# ArduinoUNO-VN_v1_1.net
KiCad netlist of a schematic drawn in Altium Designer
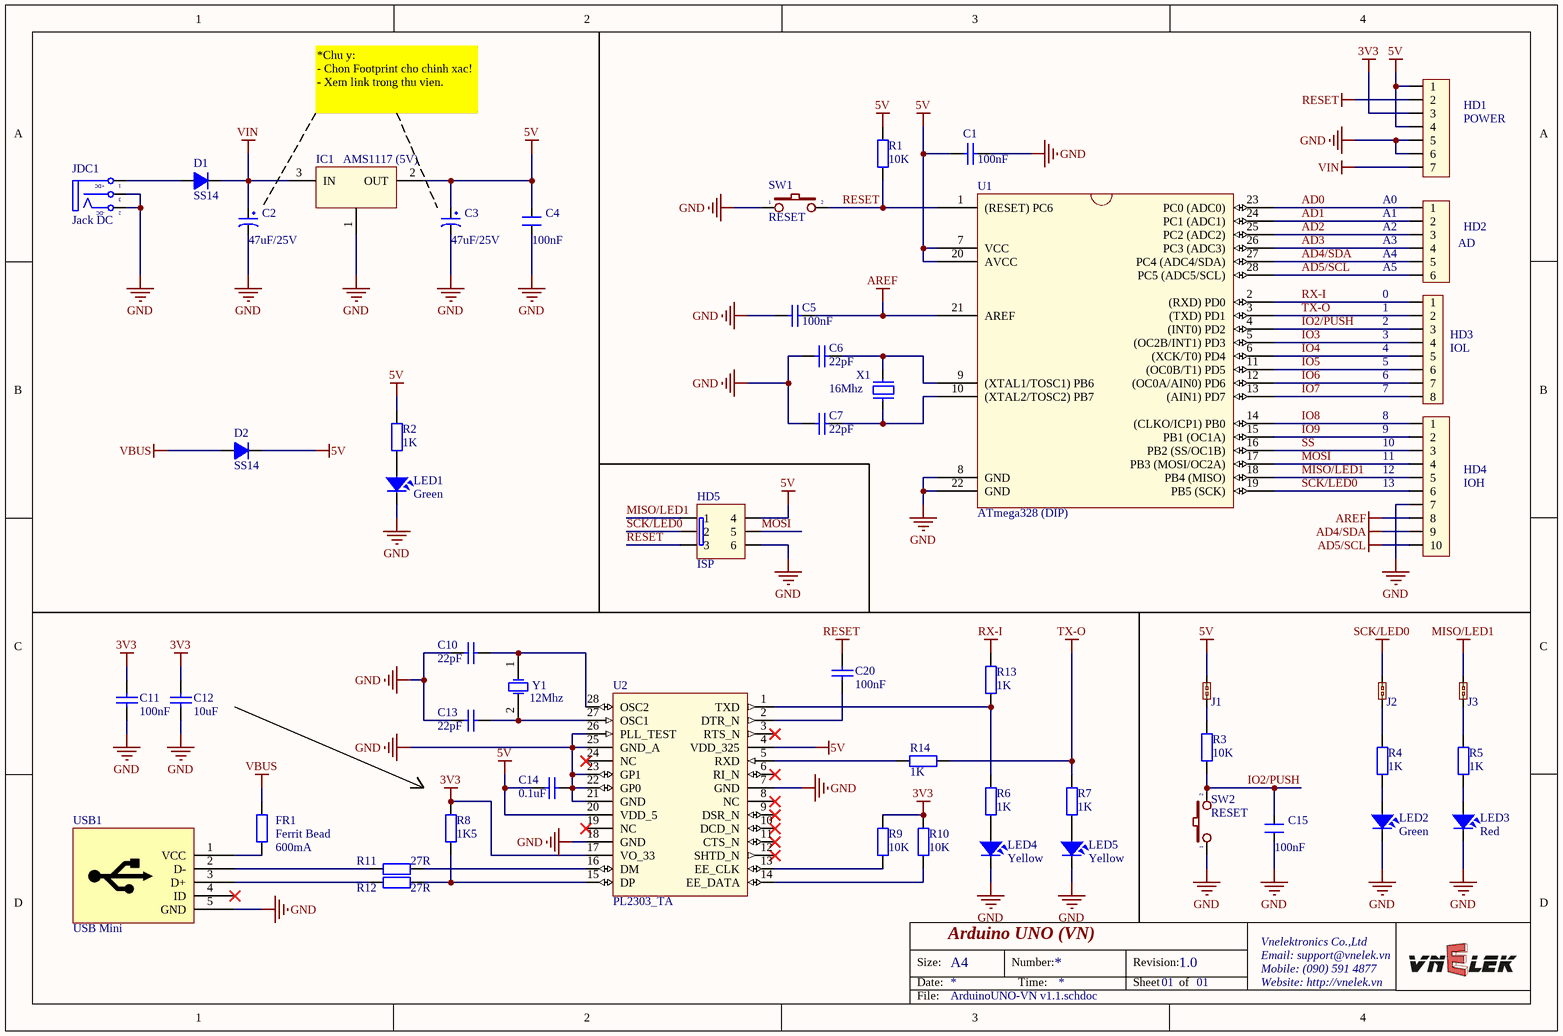
[diagram p0: ArduinoUNO-VN v1.1.schdoc]

(export (version "E")
  (design (tool "Eeschema 10.0.6"))
  (components
    (comp (ref "C1")
      (value "100nF")
      (footprint "C0603")
      (description "CAP NPO CAPNTO 1nF 100V 10%")
      (fields (field (name "Comment") "5AK102KABAA"))
      (libsource (lib "lpson") (part "5AK102KABAA"))
    )
    (comp (ref "C2") (value "47uF/25V") (libsource (lib "VNELEK") (part "CP1")))
    (comp (ref "C3") (value "47uF/25V") (libsource (lib "VNELEK") (part "CP1")))
    (comp (ref "C4")
      (value "100nF")
      (footprint "C0603")
      (description "Cap np 104 => 105pF")
      (libsource (lib "VNELEK") (part "CN2"))
    )
    (comp (ref "C5")
      (value "100nF")
      (footprint "C0603")
      (description "CAP NPO CAPNTO 1nF 100V 10%")
      (fields (field (name "Comment") "5AK102KABAA"))
      (libsource (lib "lpson") (part "5AK102KABAA"))
    )
    (comp (ref "C6")
      (value "22pF")
      (footprint "C0603")
      (description "CAP NPO CAPNTO 1nF 100V 10%")
      (fields (field (name "Comment") "5AK102KABAA"))
      (libsource (lib "lpson") (part "5AK102KABAA"))
    )
    (comp (ref "C7")
      (value "22pF")
      (footprint "C0603")
      (description "CAP NPO CAPNTO 1nF 100V 10%")
      (fields (field (name "Comment") "5AK102KABAA"))
      (libsource (lib "lpson") (part "5AK102KABAA"))
    )
    (comp (ref "C10")
      (value "22pF")
      (footprint "C0603")
      (description "22pF/50V ±5% NPO SMD-0603 Capacitor")
      (fields (field (name "Comment") "CC0603JRNPO9BN") (field (name "PUBLISHER") "Altium Limited"))
      (libsource (lib "Miscellaneous Devices") (part "Cap"))
    )
    (comp (ref "C11")
      (value "100nF")
      (footprint "C0603")
      (description "100nF/50V ±10% X7R SMD-0603 Capacitor")
      (fields (field (name "Comment") "CC0603JRNPO9BN") (field (name "PUBLISHER") "Altium Limited"))
      (libsource (lib "Miscellaneous Devices") (part "Cap"))
    )
    (comp (ref "C12")
      (value "10uF")
      (footprint "C0805")
      (description "10uF/16V ±10% X7R SMD-0805 Capacitor")
      (fields (field (name "Comment") "C0805KRX7R7BB") (field (name "PUBLISHER") "Altium Limited"))
      (libsource (lib "Miscellaneous Devices") (part "Cap"))
    )
    (comp (ref "C13")
      (value "22pF")
      (footprint "C0603")
      (description "22pF/50V ±5% NPO SMD-0603 Capacitor")
      (fields (field (name "Comment") "CC0603JRNPO9BN") (field (name "PUBLISHER") "Altium Limited"))
      (libsource (lib "Miscellaneous Devices") (part "Cap"))
    )
    (comp (ref "C14")
      (value "0.1uF")
      (footprint "C0603")
      (description "100nF/50V ±10% X7R SMD-0603 Capacitor")
      (fields (field (name "Comment") "CC0603JRNPO9BN") (field (name "PUBLISHER") "Altium Limited"))
      (libsource (lib "Miscellaneous Devices") (part "Cap"))
    )
    (comp (ref "C15")
      (value "100nF")
      (footprint "C0603")
      (description "Cap np 104 => 105pF")
      (libsource (lib "VNELEK") (part "CN2"))
    )
    (comp (ref "C20")
      (value "100nF")
      (description "100nF/50V ±10% X7R SMD-0603 Capacitor")
      (fields (field (name "Comment") "CC0603JRNPO9BN") (field (name "PUBLISHER") "Altium Limited"))
      (libsource (lib "Miscellaneous Devices") (part "Cap"))
    )
    (comp (ref "D1")
      (value "SS14")
      (footprint "SS14")
      (description "Diode 1A")
      (libsource (lib "VNELEK") (part "D1A"))
    )
    (comp (ref "D2")
      (value "SS14")
      (footprint "SS14")
      (description "Diode 1A")
      (libsource (lib "VNELEK") (part "D1A"))
    )
    (comp (ref "FR1")
      (value "Ferrit Bead")
      (footprint "CB2012")
      (fields (field (name "ALTIUM_VALUE") "600mA"))
      (libsource (lib "Miscellaneous Devices") (part "Res2"))
    )
    (comp (ref "HD1")
      (value "POWER")
      (footprint "Header_7")
      (description "Header 7")
      (libsource (lib "Tran Tuan") (part "Hed7"))
    )
    (comp (ref "HD2")
      (value "AD")
      (footprint "Header_6")
      (description "Header 6")
      (libsource (lib "Tran Tuan") (part "Hed6"))
    )
    (comp (ref "HD3")
      (value "IOL")
      (footprint "Header_8")
      (description "Hedear 8")
      (fields (field (name "CREAT BY") "VanDungEvn@Gmail.com"))
      (libsource (lib "VNELEK") (part "Hed8"))
    )
    (comp (ref "HD4")
      (value "IOH")
      (footprint "Header_10")
      (description "Header 10")
      (libsource (lib "Tran Tuan") (part "Hed10"))
    )
    (comp (ref "HD5")
      (value "ISP")
      (footprint "Header_3x2")
      (description "Header 3x2")
      (libsource (lib "Tran Tuan") (part "HED3x2"))
    )
    (comp (ref "IC1")
      (value "AMS1117 (5V)")
      (footprint "AMS1117-5.0V")
      (description "1A LOW DROPOUT VOLTAGE REGULATOR")
      (libsource (lib "Tran Tuan") (part "AMS1117"))
    )
    (comp (ref "J1")
      (value "Short Jump")
      (footprint "Header_2")
      (libsource (lib "Tran Tuan") (part "ShortJump"))
    )
    (comp (ref "J2")
      (value "Short Jump")
      (footprint "Header_2")
      (libsource (lib "Tran Tuan") (part "ShortJump"))
    )
    (comp (ref "J3")
      (value "Short Jump")
      (footprint "Header_2")
      (libsource (lib "Tran Tuan") (part "ShortJump"))
    )
    (comp (ref "JDC1")
      (value "Jack DC")
      (footprint "DC-IN")
      (description "Jac DC input")
      (libsource (lib "VNELEK") (part "DCIN"))
    )
    (comp (ref "LED1")
      (value "Green")
      (footprint "Led 0805Y")
      (description "LED Single colour Green and Red")
      (libsource (lib "VNELEK") (part "LED"))
    )
    (comp (ref "LED2")
      (value "Green")
      (footprint "Led 0805G")
      (description "LED Single colour Green and Red")
      (libsource (lib "VNELEK") (part "LED"))
    )
    (comp (ref "LED3")
      (value "Red")
      (footprint "Led 0805R")
      (description "LED Single colour Green and Red")
      (libsource (lib "VNELEK") (part "LED"))
    )
    (comp (ref "LED4")
      (value "Yellow")
      (footprint "Led 0805G")
      (description "LED Single colour Green and Red")
      (libsource (lib "VNELEK") (part "LED"))
    )
    (comp (ref "LED5")
      (value "Yellow")
      (footprint "Led 0805R")
      (description "LED Single colour Green and Red")
      (libsource (lib "VNELEK") (part "LED"))
    )
    (comp (ref "R1")
      (value "10K")
      (footprint "RESC2012L")
      (description "Resistor")
      (fields (field (name "Comment") "Res2") (field (name "PUBLISHER") "Altium Limited"))
      (libsource (lib "Miscellaneous Devices") (part "Res2"))
    )
    (comp (ref "R2")
      (value "1K")
      (footprint "RESC2012L")
      (description "Resistor")
      (fields (field (name "Comment") "Res2") (field (name "PUBLISHER") "Altium Limited"))
      (libsource (lib "Miscellaneous Devices") (part "Res2"))
    )
    (comp (ref "R3")
      (value "10K")
      (footprint "RM06JTN (0603)")
      (description "Resistor")
      (fields (field (name "Comment") "Res2") (field (name "PUBLISHER") "Altium Limited"))
      (libsource (lib "Miscellaneous Devices") (part "Res2"))
    )
    (comp (ref "R4")
      (value "1K")
      (footprint "RM06JTN (0603)")
      (description "Resistor")
      (fields (field (name "Comment") "Res2") (field (name "PUBLISHER") "Altium Limited"))
      (libsource (lib "Miscellaneous Devices") (part "Res2"))
    )
    (comp (ref "R5")
      (value "1K")
      (footprint "RM06JTN (0603)")
      (description "Resistor")
      (fields (field (name "Comment") "Res2") (field (name "PUBLISHER") "Altium Limited"))
      (libsource (lib "Miscellaneous Devices") (part "Res2"))
    )
    (comp (ref "R6")
      (value "1K")
      (footprint "RM06JTN (0603)")
      (description "Resistor")
      (fields (field (name "Comment") "Res2") (field (name "PUBLISHER") "Altium Limited"))
      (libsource (lib "Miscellaneous Devices") (part "Res2"))
    )
    (comp (ref "R7")
      (value "1K")
      (footprint "RM06JTN (0603)")
      (description "Resistor")
      (fields (field (name "Comment") "Res2") (field (name "PUBLISHER") "Altium Limited"))
      (libsource (lib "Miscellaneous Devices") (part "Res2"))
    )
    (comp (ref "R8")
      (value "1K5")
      (footprint "RM06JTN (0603)")
      (description "1.5K ±5% SMD-0603 Resistor")
      (fields (field (name "Comment") "RM06JTN") (field (name "PUBLISHER") "Altium Limited"))
      (libsource (lib "") (part "Res2_1"))
    )
    (comp (ref "R9")
      (value "10K")
      (footprint "RM06JTN (0603)")
      (description "10K ±5% SMD-0603 Resistor")
      (fields (field (name "Comment") "RM06JTN") (field (name "PUBLISHER") "Altium Limited"))
      (libsource (lib "") (part "Res2_2"))
    )
    (comp (ref "R10")
      (value "10K")
      (footprint "RM06JTN (0603)")
      (description "10K ±5% SMD-0603 Resistor")
      (fields (field (name "Comment") "RM06JTN") (field (name "PUBLISHER") "Altium Limited"))
      (libsource (lib "") (part "Res2_2"))
    )
    (comp (ref "R11")
      (value "27R")
      (footprint "RM06JTN (0603)")
      (description "Resistor")
      (fields (field (name "Comment") "Res2") (field (name "PUBLISHER") "Altium Limited"))
      (libsource (lib "") (part "Res2_2"))
    )
    (comp (ref "R12")
      (value "27R")
      (footprint "RM06JTN (0603)")
      (description "Resistor")
      (fields (field (name "Comment") "Res2") (field (name "PUBLISHER") "Altium Limited"))
      (libsource (lib "") (part "Res2_2"))
    )
    (comp (ref "R13")
      (value "1K")
      (footprint "RM06JTN (0603)")
      (description "Resistor")
      (fields (field (name "Comment") "Res2") (field (name "PUBLISHER") "Altium Limited"))
      (libsource (lib "") (part "Res2_1"))
    )
    (comp (ref "R14")
      (value "1K")
      (footprint "RM06JTN (0603)")
      (description "Resistor")
      (fields (field (name "Comment") "Res2") (field (name "PUBLISHER") "Altium Limited"))
      (libsource (lib "") (part "Res2_2"))
    )
    (comp (ref "SW1")
      (value "RESET")
      (footprint "BUTTON 2PIN TRON")
      (description "Switch button 2 pin")
      (libsource (lib "VNELEK") (part "SW2"))
    )
    (comp (ref "SW2")
      (value "RESET")
      (footprint "BUTTON 2PIN TRON")
      (description "Switch button 2 pin")
      (libsource (lib "VNELEK") (part "SW2"))
    )
    (comp (ref "U1")
      (value "ATmega328 (DIP)")
      (footprint "ATmega328 (DIP)")
      (description "Atmel 8-bit Microcontroller")
      (libsource (lib "Tran Tuan") (part "ATmega328_1"))
    )
    (comp (ref "U2")
      (value "PL2303_TA")
      (footprint "PL2303HX")
      (description "USB to UART,28pin,EEPROM extract")
      (libsource (lib "PL2303HXA") (part "PL2303_HXA"))
    )
    (comp (ref "USB1") (value "USB Mini") (footprint "USBMNIB") (libsource (lib "VNELEK") (part "USB_M")))
    (comp (ref "X1")
      (value "16Mhz")
      (footprint "CRYSTAL")
      (description "Crystal SMD")
      (libsource (lib "lpson") (part "XT2"))
    )
    (comp (ref "Y1")
      (value "12Mhz")
      (footprint "CSTCE16M0V53-R0")
      (description "12Mhz SMD")
      (libsource (lib "Miscellaneous Devices") (part "XTAL"))
    )
  )
  (nets
    (net (code "1") (name "/AD0") (class "Default")
      (node (ref "HD2") (pin "1") (pinfunction "1_1") (pintype "passive"))
      (node (ref "U1") (pin "23") (pinfunction "PC0_(ADC0)_23") (pintype "bidirectional"))
    )
    (net (code "2") (name "/AD1") (class "Default")
      (node (ref "HD2") (pin "2") (pinfunction "2_2") (pintype "passive"))
      (node (ref "U1") (pin "24") (pinfunction "PC1_(ADC1)_24") (pintype "bidirectional"))
    )
    (net (code "3") (name "/AD2") (class "Default")
      (node (ref "HD2") (pin "3") (pinfunction "3_3") (pintype "passive"))
      (node (ref "U1") (pin "25") (pinfunction "PC2_(ADC2)_25") (pintype "bidirectional"))
    )
    (net (code "4") (name "/AD3") (class "Default")
      (node (ref "HD2") (pin "4") (pinfunction "4_4") (pintype "passive"))
      (node (ref "U1") (pin "26") (pinfunction "PC3_(ADC3)_26") (pintype "bidirectional"))
    )
    (net (code "5") (name "/IO2{slash}PUSH") (class "Default")
      (node (ref "C15") (pin "2") (pinfunction "2_2") (pintype "passive"))
      (node (ref "HD3") (pin "3") (pinfunction "3_3") (pintype "passive"))
      (node (ref "R3") (pin "1") (pinfunction "1_1") (pintype "passive"))
      (node (ref "SW2") (pin "2") (pinfunction "2_2") (pintype "passive"))
      (node (ref "U1") (pin "4") (pinfunction "(INT0)_PD2_4") (pintype "bidirectional"))
    )
    (net (code "6") (name "/IO3") (class "Default")
      (node (ref "HD3") (pin "4") (pinfunction "4_4") (pintype "passive"))
      (node (ref "U1") (pin "5") (pinfunction "(OC2B/INT1)_PD3_5") (pintype "bidirectional"))
    )
    (net (code "7") (name "/IO4") (class "Default")
      (node (ref "HD3") (pin "5") (pinfunction "5_5") (pintype "passive"))
      (node (ref "U1") (pin "6") (pinfunction "(XCK/T0)_PD4_6") (pintype "bidirectional"))
    )
    (net (code "8") (name "/IO5") (class "Default")
      (node (ref "HD3") (pin "6") (pinfunction "6_6") (pintype "passive"))
      (node (ref "U1") (pin "11") (pinfunction "(OC0B/T1)_PD5_11") (pintype "bidirectional"))
    )
    (net (code "9") (name "/IO6") (class "Default")
      (node (ref "HD3") (pin "7") (pinfunction "7_7") (pintype "passive"))
      (node (ref "U1") (pin "12") (pinfunction "(OC0A/AIN0)_PD6_12") (pintype "bidirectional"))
    )
    (net (code "10") (name "/IO7") (class "Default")
      (node (ref "HD3") (pin "8") (pinfunction "8_8") (pintype "passive"))
      (node (ref "U1") (pin "13") (pinfunction "(AIN1)_PD7_13") (pintype "bidirectional"))
    )
    (net (code "11") (name "/IO8") (class "Default")
      (node (ref "HD4") (pin "1") (pinfunction "1_1") (pintype "passive"))
      (node (ref "U1") (pin "14") (pinfunction "(CLKO/ICP1)_PB0_14") (pintype "bidirectional"))
    )
    (net (code "12") (name "/IO9") (class "Default")
      (node (ref "HD4") (pin "2") (pinfunction "2_2") (pintype "passive"))
      (node (ref "U1") (pin "15") (pinfunction "PB1_(OC1A)_15") (pintype "bidirectional"))
    )
    (net (code "13") (name "/MOSI") (class "Default")
      (node (ref "HD4") (pin "4") (pinfunction "4_4") (pintype "passive"))
      (node (ref "HD5") (pin "5") (pinfunction "5_5") (pintype "passive"))
      (node (ref "U1") (pin "17") (pinfunction "PB3_(MOSI/OC2A)_17") (pintype "bidirectional"))
    )
    (net (code "14") (name "/SS") (class "Default")
      (node (ref "HD4") (pin "3") (pinfunction "3_3") (pintype "passive"))
      (node (ref "U1") (pin "16") (pinfunction "PB2_(SS/OC1B)_16") (pintype "bidirectional"))
    )
    (net (code "15") (name "3V3") (class "Default")
      (node (ref "C11") (pin "2") (pinfunction "2_2") (pintype "passive"))
      (node (ref "C12") (pin "1") (pinfunction "1_1") (pintype "passive"))
      (node (ref "HD1") (pin "3") (pinfunction "3_3") (pintype "passive"))
      (node (ref "R10") (pin "1") (pinfunction "1_1") (pintype "passive"))
      (node (ref "R8") (pin "1") (pinfunction "1_1") (pintype "passive"))
      (node (ref "R9") (pin "1") (pinfunction "1_1") (pintype "passive"))
      (node (ref "U2") (pin "17") (pinfunction "VO_33_17") (pintype "passive"))
    )
    (net (code "16") (name "5V") (class "Default")
      (node (ref "C1") (pin "2") (pinfunction "2_2") (pintype "passive"))
      (node (ref "C14") (pin "1") (pinfunction "1_1") (pintype "passive"))
      (node (ref "C3") (pin "1") (pinfunction "1_1") (pintype "passive"))
      (node (ref "C4") (pin "2") (pinfunction "2_2") (pintype "passive"))
      (node (ref "D2") (pin "2") (pinfunction "K_2") (pintype "passive"))
      (node (ref "HD1") (pin "1") (pinfunction "1_1") (pintype "passive"))
      (node (ref "HD1") (pin "4") (pinfunction "4_4") (pintype "passive"))
      (node (ref "HD5") (pin "4") (pinfunction "4_4") (pintype "passive"))
      (node (ref "IC1") (pin "2") (pinfunction "OUT_2") (pintype "passive"))
      (node (ref "J1") (pin "2") (pinfunction "2_2") (pintype "passive"))
      (node (ref "R1") (pin "2") (pinfunction "2_2") (pintype "passive"))
      (node (ref "R2") (pin "2") (pinfunction "2_2") (pintype "passive"))
      (node (ref "U1") (pin "20") (pinfunction "AVCC_20") (pintype "passive"))
      (node (ref "U1") (pin "7") (pinfunction "VCC_7") (pintype "passive"))
      (node (ref "U2") (pin "20") (pinfunction "VDD_5_20") (pintype "passive"))
      (node (ref "U2") (pin "4") (pinfunction "VDD_325_4") (pintype "passive"))
    )
    (net (code "17") (name "AD4{slash}SDA") (class "Default")
      (node (ref "HD2") (pin "5") (pinfunction "5_5") (pintype "passive"))
      (node (ref "HD4") (pin "9") (pinfunction "9_9") (pintype "passive"))
      (node (ref "U1") (pin "27") (pinfunction "PC4_(ADC4/SDA)_27") (pintype "bidirectional"))
    )
    (net (code "18") (name "AD5{slash}SCL") (class "Default")
      (node (ref "HD2") (pin "6") (pinfunction "6_6") (pintype "passive"))
      (node (ref "HD4") (pin "10") (pinfunction "10_10") (pintype "passive"))
      (node (ref "U1") (pin "28") (pinfunction "PC5_(ADC5/SCL)_28") (pintype "bidirectional"))
    )
    (net (code "19") (name "AREF") (class "Default")
      (node (ref "C5") (pin "2") (pinfunction "2_2") (pintype "passive"))
      (node (ref "HD4") (pin "8") (pinfunction "8_8") (pintype "passive"))
      (node (ref "U1") (pin "21") (pinfunction "AREF_21") (pintype "passive"))
    )
    (net (code "20") (name "GND") (class "Default")
      (node (ref "C1") (pin "1") (pinfunction "1_1") (pintype "passive"))
      (node (ref "C10") (pin "1") (pinfunction "1_1") (pintype "passive"))
      (node (ref "C11") (pin "1") (pinfunction "1_1") (pintype "passive"))
      (node (ref "C12") (pin "2") (pinfunction "2_2") (pintype "passive"))
      (node (ref "C13") (pin "1") (pinfunction "1_1") (pintype "passive"))
      (node (ref "C14") (pin "2") (pinfunction "2_2") (pintype "passive"))
      (node (ref "C15") (pin "1") (pinfunction "1_1") (pintype "passive"))
      (node (ref "C2") (pin "2") (pinfunction "2_2") (pintype "passive"))
      (node (ref "C3") (pin "2") (pinfunction "2_2") (pintype "passive"))
      (node (ref "C4") (pin "1") (pinfunction "1_1") (pintype "passive"))
      (node (ref "C5") (pin "1") (pinfunction "1_1") (pintype "passive"))
      (node (ref "C6") (pin "1") (pinfunction "1_1") (pintype "passive"))
      (node (ref "C7") (pin "1") (pinfunction "1_1") (pintype "passive"))
      (node (ref "HD1") (pin "5") (pinfunction "5_5") (pintype "passive"))
      (node (ref "HD1") (pin "6") (pinfunction "6_6") (pintype "passive"))
      (node (ref "HD4") (pin "7") (pinfunction "7_7") (pintype "passive"))
      (node (ref "HD5") (pin "6") (pinfunction "6_6") (pintype "passive"))
      (node (ref "IC1") (pin "1") (pinfunction "GND_1") (pintype "passive"))
      (node (ref "JDC1") (pin "2") (pinfunction "TN_2") (pintype "passive"))
      (node (ref "JDC1") (pin "3") (pinfunction "S_3") (pintype "power_in"))
      (node (ref "LED1") (pin "2") (pinfunction "2_2") (pintype "passive"))
      (node (ref "LED2") (pin "2") (pinfunction "2_2") (pintype "passive"))
      (node (ref "LED3") (pin "2") (pinfunction "2_2") (pintype "passive"))
      (node (ref "LED4") (pin "2") (pinfunction "2_2") (pintype "passive"))
      (node (ref "LED5") (pin "2") (pinfunction "2_2") (pintype "passive"))
      (node (ref "SW1") (pin "1") (pinfunction "1_1") (pintype "passive"))
      (node (ref "SW2") (pin "1") (pinfunction "1_1") (pintype "passive"))
      (node (ref "U1") (pin "22") (pinfunction "GND_22") (pintype "passive"))
      (node (ref "U1") (pin "8") (pinfunction "GND_8") (pintype "passive"))
      (node (ref "U2") (pin "18") (pinfunction "GND_18") (pintype "passive"))
      (node (ref "U2") (pin "21") (pinfunction "GND_21") (pintype "passive"))
      (node (ref "U2") (pin "22") (pinfunction "GP0_22") (pintype "bidirectional"))
      (node (ref "U2") (pin "23") (pinfunction "GP1_23") (pintype "bidirectional"))
      (node (ref "U2") (pin "25") (pinfunction "GND_A_25") (pintype "passive"))
      (node (ref "U2") (pin "26") (pinfunction "PLL_TEST_26") (pintype "input"))
      (node (ref "U2") (pin "7") (pinfunction "GND_7") (pintype "passive"))
      (node (ref "USB1") (pin "5") (pinfunction "GND_5") (pintype "passive"))
    )
    (net (code "21") (name "MISO{slash}LED1") (class "Default")
      (node (ref "HD4") (pin "5") (pinfunction "5_5") (pintype "passive"))
      (node (ref "HD5") (pin "1") (pinfunction "1_1") (pintype "passive"))
      (node (ref "J3") (pin "2") (pinfunction "2_2") (pintype "passive"))
      (node (ref "U1") (pin "18") (pinfunction "PB4_(MISO)_18") (pintype "bidirectional"))
    )
    (net (code "22") (name "Net-(D1-A)") (class "Default")
      (node (ref "D1") (pin "1") (pinfunction "A_1") (pintype "passive"))
      (node (ref "JDC1") (pin "1") (pinfunction "T_1") (pintype "passive"))
    )
    (net (code "23") (name "Net-(J1-Pad1)") (class "Default")
      (node (ref "J1") (pin "1") (pinfunction "1_1") (pintype "passive"))
      (node (ref "R3") (pin "2") (pinfunction "2_2") (pintype "passive"))
    )
    (net (code "24") (name "Net-(J2-Pad1)") (class "Default")
      (node (ref "J2") (pin "1") (pinfunction "1_1") (pintype "passive"))
      (node (ref "R4") (pin "2") (pinfunction "2_2") (pintype "passive"))
    )
    (net (code "25") (name "Net-(J3-Pad1)") (class "Default")
      (node (ref "J3") (pin "1") (pinfunction "1_1") (pintype "passive"))
      (node (ref "R5") (pin "2") (pinfunction "2_2") (pintype "passive"))
    )
    (net (code "26") (name "Net-(LED1-Pad1)") (class "Default")
      (node (ref "LED1") (pin "1") (pinfunction "1_1") (pintype "passive"))
      (node (ref "R2") (pin "1") (pinfunction "1_1") (pintype "passive"))
    )
    (net (code "27") (name "Net-(LED2-Pad1)") (class "Default")
      (node (ref "LED2") (pin "1") (pinfunction "1_1") (pintype "passive"))
      (node (ref "R4") (pin "1") (pinfunction "1_1") (pintype "passive"))
    )
    (net (code "28") (name "Net-(LED3-Pad1)") (class "Default")
      (node (ref "LED3") (pin "1") (pinfunction "1_1") (pintype "passive"))
      (node (ref "R5") (pin "1") (pinfunction "1_1") (pintype "passive"))
    )
    (net (code "29") (name "Net-(LED4-Pad1)") (class "Default")
      (node (ref "LED4") (pin "1") (pinfunction "1_1") (pintype "passive"))
      (node (ref "R6") (pin "1") (pinfunction "1_1") (pintype "passive"))
    )
    (net (code "30") (name "Net-(LED5-Pad1)") (class "Default")
      (node (ref "LED5") (pin "1") (pinfunction "1_1") (pintype "passive"))
      (node (ref "R7") (pin "1") (pinfunction "1_1") (pintype "passive"))
    )
    (net (code "31") (name "Net-(U1-(XTAL1{slash}TOSC1)_PB6)") (class "Default")
      (node (ref "C6") (pin "2") (pinfunction "2_2") (pintype "passive"))
      (node (ref "U1") (pin "9") (pinfunction "(XTAL1/TOSC1)_PB6_9") (pintype "passive"))
      (node (ref "X1") (pin "2") (pinfunction "2_2") (pintype "passive"))
    )
    (net (code "32") (name "Net-(U1-(XTAL2{slash}TOSC2)_PB7)") (class "Default")
      (node (ref "C7") (pin "2") (pinfunction "2_2") (pintype "passive"))
      (node (ref "U1") (pin "10") (pinfunction "(XTAL2/TOSC2)_PB7_10") (pintype "passive"))
      (node (ref "X1") (pin "1") (pinfunction "1_1") (pintype "passive"))
    )
    (net (code "33") (name "Net-(U2-DM)") (class "Default")
      (node (ref "R11") (pin "1") (pinfunction "1_1") (pintype "passive"))
      (node (ref "U2") (pin "16") (pinfunction "DM_16") (pintype "bidirectional"))
    )
    (net (code "34") (name "Net-(U2-DP)") (class "Default")
      (node (ref "R12") (pin "1") (pinfunction "1_1") (pintype "passive"))
      (node (ref "R8") (pin "2") (pinfunction "2_2") (pintype "passive"))
      (node (ref "U2") (pin "15") (pinfunction "DP_15") (pintype "bidirectional"))
    )
    (net (code "35") (name "Net-(U2-DTR_N)") (class "Default")
      (node (ref "C20") (pin "1") (pinfunction "1_1") (pintype "passive"))
      (node (ref "U2") (pin "2") (pinfunction "DTR_N_2") (pintype "output"))
    )
    (net (code "36") (name "Net-(U2-EE_CLK)") (class "Default")
      (node (ref "R9") (pin "2") (pinfunction "2_2") (pintype "passive"))
      (node (ref "U2") (pin "13") (pinfunction "EE_CLK_13") (pintype "bidirectional"))
    )
    (net (code "37") (name "Net-(U2-EE_DATA)") (class "Default")
      (node (ref "R10") (pin "2") (pinfunction "2_2") (pintype "passive"))
      (node (ref "U2") (pin "14") (pinfunction "EE_DATA_14") (pintype "bidirectional"))
    )
    (net (code "38") (name "Net-(U2-OSC1)") (class "Default")
      (node (ref "C13") (pin "2") (pinfunction "2_2") (pintype "passive"))
      (node (ref "U2") (pin "27") (pinfunction "OSC1_27") (pintype "input"))
      (node (ref "Y1") (pin "2") (pinfunction "OSC2_2") (pintype "passive"))
    )
    (net (code "39") (name "Net-(U2-OSC2)") (class "Default")
      (node (ref "C10") (pin "2") (pinfunction "2_2") (pintype "passive"))
      (node (ref "U2") (pin "28") (pinfunction "OSC2_28") (pintype "bidirectional"))
      (node (ref "Y1") (pin "1") (pinfunction "OSC1_1") (pintype "passive"))
    )
    (net (code "40") (name "Net-(U2-RXD)") (class "Default")
      (node (ref "R14") (pin "2") (pinfunction "2_2") (pintype "passive"))
      (node (ref "U2") (pin "5") (pinfunction "RXD_5") (pintype "input"))
    )
    (net (code "41") (name "Net-(U2-TXD)") (class "Default")
      (node (ref "R13") (pin "2") (pinfunction "2_2") (pintype "passive"))
      (node (ref "R6") (pin "2") (pinfunction "2_2") (pintype "passive"))
      (node (ref "U2") (pin "1") (pinfunction "TXD_1") (pintype "output"))
    )
    (net (code "42") (name "Net-(USB1-D+)") (class "Default")
      (node (ref "R12") (pin "2") (pinfunction "2_2") (pintype "passive"))
      (node (ref "USB1") (pin "3") (pinfunction "D+_3") (pintype "passive"))
    )
    (net (code "43") (name "Net-(USB1-D-)") (class "Default")
      (node (ref "R11") (pin "2") (pinfunction "2_2") (pintype "passive"))
      (node (ref "USB1") (pin "2") (pinfunction "D-_2") (pintype "passive"))
    )
    (net (code "44") (name "Net-(USB1-VCC)") (class "Default")
      (node (ref "FR1") (pin "1") (pinfunction "1_1") (pintype "passive"))
      (node (ref "USB1") (pin "1") (pinfunction "VCC_1") (pintype "passive"))
    )
    (net (code "45") (name "RESET") (class "Default")
      (node (ref "C20") (pin "2") (pinfunction "2_2") (pintype "passive"))
      (node (ref "HD1") (pin "2") (pinfunction "2_2") (pintype "passive"))
      (node (ref "HD5") (pin "3") (pinfunction "3_3") (pintype "passive"))
      (node (ref "R1") (pin "1") (pinfunction "1_1") (pintype "passive"))
      (node (ref "SW1") (pin "2") (pinfunction "2_2") (pintype "passive"))
      (node (ref "U1") (pin "1") (pinfunction "(RESET)_PC6_1") (pintype "passive"))
    )
    (net (code "46") (name "RX-I") (class "Default")
      (node (ref "HD3") (pin "1") (pinfunction "1_1") (pintype "passive"))
      (node (ref "R13") (pin "1") (pinfunction "1_1") (pintype "passive"))
      (node (ref "U1") (pin "2") (pinfunction "(RXD)_PD0_2") (pintype "bidirectional"))
    )
    (net (code "47") (name "SCK{slash}LED0") (class "Default")
      (node (ref "HD4") (pin "6") (pinfunction "6_6") (pintype "passive"))
      (node (ref "HD5") (pin "2") (pinfunction "2_2") (pintype "passive"))
      (node (ref "J2") (pin "2") (pinfunction "2_2") (pintype "passive"))
      (node (ref "U1") (pin "19") (pinfunction "PB5_(SCK)_19") (pintype "bidirectional"))
    )
    (net (code "48") (name "TX-O") (class "Default")
      (node (ref "HD3") (pin "2") (pinfunction "2_2") (pintype "passive"))
      (node (ref "R14") (pin "1") (pinfunction "1_1") (pintype "passive"))
      (node (ref "R7") (pin "2") (pinfunction "2_2") (pintype "passive"))
      (node (ref "U1") (pin "3") (pinfunction "(TXD)_PD1_3") (pintype "bidirectional"))
    )
    (net (code "49") (name "VBUS") (class "Default")
      (node (ref "D2") (pin "1") (pinfunction "A_1") (pintype "passive"))
      (node (ref "FR1") (pin "2") (pinfunction "2_2") (pintype "passive"))
    )
    (net (code "50") (name "VIN") (class "Default")
      (node (ref "C2") (pin "1") (pinfunction "1_1") (pintype "passive"))
      (node (ref "D1") (pin "2") (pinfunction "K_2") (pintype "passive"))
      (node (ref "HD1") (pin "7") (pinfunction "7_7") (pintype "passive"))
      (node (ref "IC1") (pin "3") (pinfunction "IN_3") (pintype "passive"))
    )
    (net (code "51") (name "unconnected-(U2-CTS_N-Pad11)") (class "Default")
      (node (ref "U2") (pin "11") (pinfunction "CTS_N_11") (pintype "bidirectional+no_connect"))
    )
    (net (code "52") (name "unconnected-(U2-DCD_N-Pad10)") (class "Default")
      (node (ref "U2") (pin "10") (pinfunction "DCD_N_10") (pintype "bidirectional+no_connect"))
    )
    (net (code "53") (name "unconnected-(U2-DSR_N-Pad9)") (class "Default")
      (node (ref "U2") (pin "9") (pinfunction "DSR_N_9") (pintype "bidirectional+no_connect"))
    )
    (net (code "54") (name "unconnected-(U2-NC-Pad8)") (class "Default")
      (node (ref "U2") (pin "8") (pinfunction "NC_8") (pintype "passive+no_connect"))
    )
    (net (code "55") (name "unconnected-(U2-NC-Pad19)") (class "Default")
      (node (ref "U2") (pin "19") (pinfunction "NC_19") (pintype "passive+no_connect"))
    )
    (net (code "56") (name "unconnected-(U2-NC-Pad24)") (class "Default")
      (node (ref "U2") (pin "24") (pinfunction "NC_24") (pintype "passive+no_connect"))
    )
    (net (code "57") (name "unconnected-(U2-RI_N-Pad6)") (class "Default")
      (node (ref "U2") (pin "6") (pinfunction "RI_N_6") (pintype "bidirectional+no_connect"))
    )
    (net (code "58") (name "unconnected-(U2-RTS_N-Pad3)") (class "Default")
      (node (ref "U2") (pin "3") (pinfunction "RTS_N_3") (pintype "output+no_connect"))
    )
    (net (code "59") (name "unconnected-(U2-SHTD_N-Pad12)") (class "Default")
      (node (ref "U2") (pin "12") (pinfunction "SHTD_N_12") (pintype "output+no_connect"))
    )
    (net (code "60") (name "unconnected-(USB1-ID-Pad4)") (class "Default")
      (node (ref "USB1") (pin "4") (pinfunction "ID_4") (pintype "passive+no_connect"))
    )
  )
)
